# CS4244.net
KiCad netlist of a schematic drawn in EAGLE
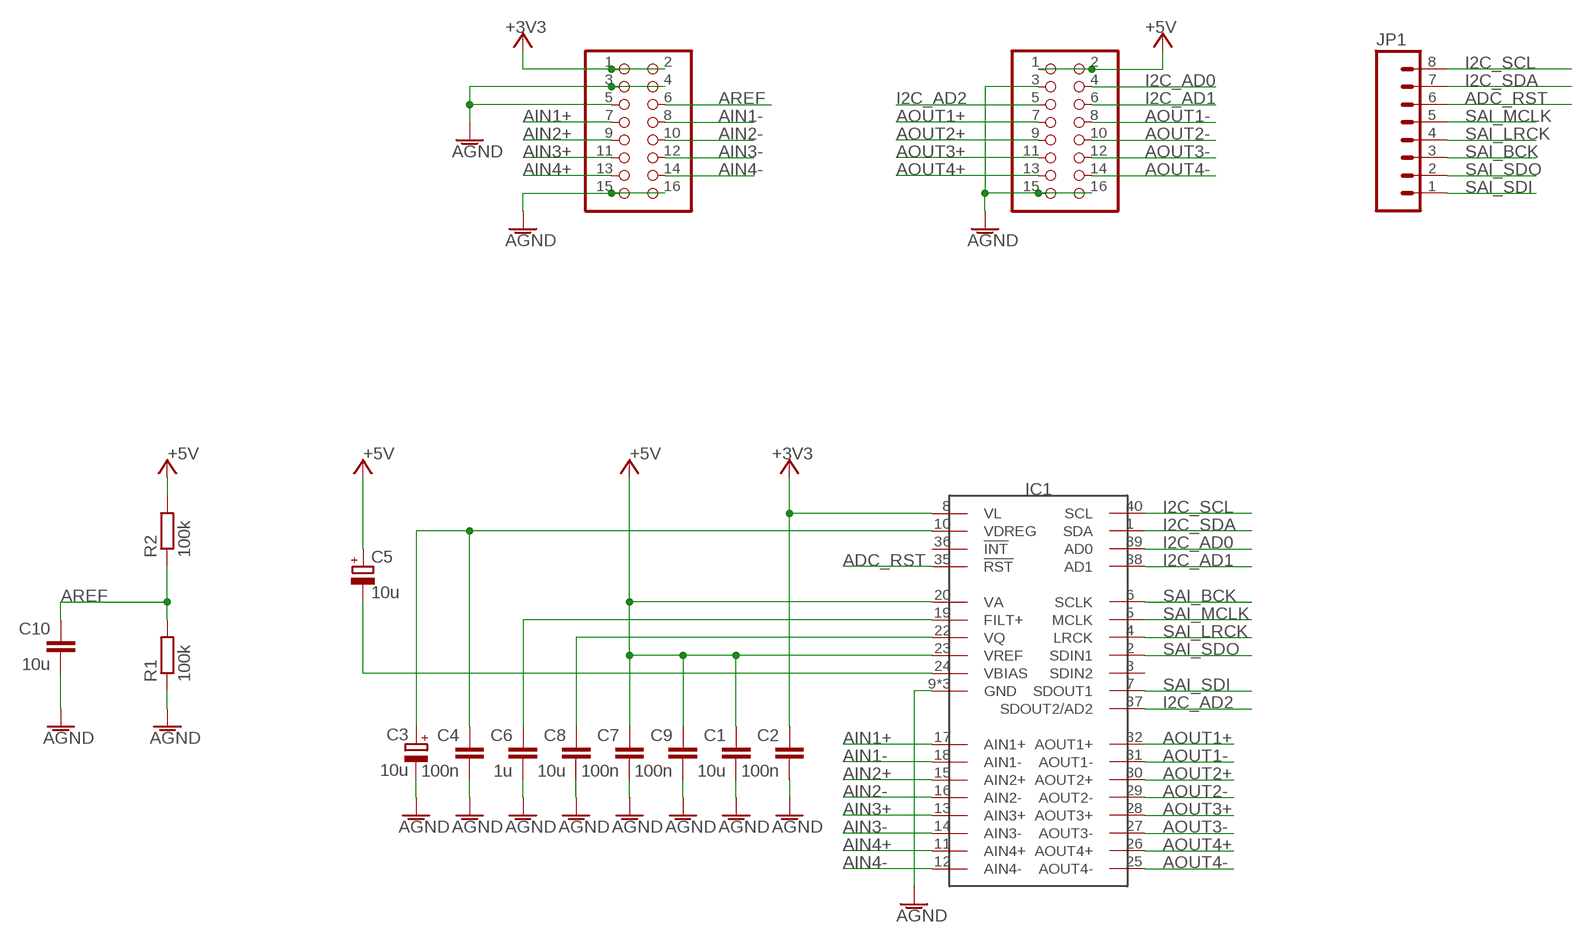
[diagram p0: schematic, sheet 1]

(export (version "E")
  (design (tool "Eeschema 10.0.6"))
  (components
    (comp (ref "C1")
      (value "10u")
      (footprint "eagle-import:C0603")
      (libsource (lib "eagle-import") (part "C-EUC0603"))
    )
    (comp (ref "C2")
      (value "100n")
      (footprint "eagle-import:C0603")
      (libsource (lib "eagle-import") (part "C-EUC0603"))
    )
    (comp (ref "C3")
      (value "10u")
      (footprint "eagle-import:UD-4X5,8_NICHICON")
      (libsource (lib "eagle-import") (part "CPOL-EUUD-4X5,8"))
    )
    (comp (ref "C4")
      (value "100n")
      (footprint "eagle-import:C0603")
      (libsource (lib "eagle-import") (part "C-EUC0603"))
    )
    (comp (ref "C5")
      (value "10u")
      (footprint "eagle-import:UD-4X5,8_NICHICON")
      (libsource (lib "eagle-import") (part "CPOL-EUUD-4X5,8"))
    )
    (comp (ref "C6")
      (value "1u")
      (footprint "eagle-import:C0603")
      (libsource (lib "eagle-import") (part "C-EUC0603"))
    )
    (comp (ref "C7")
      (value "100n")
      (footprint "eagle-import:C0603")
      (libsource (lib "eagle-import") (part "C-EUC0603"))
    )
    (comp (ref "C8")
      (value "10u")
      (footprint "eagle-import:C0603")
      (libsource (lib "eagle-import") (part "C-EUC0603"))
    )
    (comp (ref "C9")
      (value "100n")
      (footprint "eagle-import:C0603")
      (libsource (lib "eagle-import") (part "C-EUC0603"))
    )
    (comp (ref "C10")
      (value "10u")
      (footprint "eagle-import:C0603")
      (libsource (lib "eagle-import") (part "C-EUC0603"))
    )
    (comp (ref "IC1")
      (value "CS4244")
      (footprint "eagle-import:QFN50P600X600X100-41N")
      (libsource (lib "eagle-import") (part "CS4244"))
    )
    (comp (ref "JP1")
      (value "M081X08")
      (footprint "eagle-import:1X08")
      (libsource (lib "eagle-import") (part "M081X08"))
    )
    (comp (ref "JP2")
      (value "PINHD-2X8")
      (footprint "eagle-import:2X08")
      (libsource (lib "eagle-import") (part "PINHD-2X8"))
    )
    (comp (ref "JP3")
      (value "PINHD-2X8")
      (footprint "eagle-import:2X08")
      (libsource (lib "eagle-import") (part "PINHD-2X8"))
    )
    (comp (ref "R1")
      (value "100k")
      (footprint "eagle-import:0603")
      (libsource (lib "eagle-import") (part "R-EU_R0603"))
    )
    (comp (ref "R2")
      (value "100k")
      (footprint "eagle-import:0603")
      (libsource (lib "eagle-import") (part "R-EU_R0603"))
    )
  )
  (nets
    (net (code "1") (name "+3V3") (class "Default")
      (node (ref "C2") (pin "1") (pinfunction "1_1") (pintype "passive"))
      (node (ref "IC1") (pin "8") (pinfunction "VL_8") (pintype "bidirectional"))
      (node (ref "JP2") (pin "1") (pinfunction "1_1") (pintype "passive"))
      (node (ref "JP2") (pin "2") (pinfunction "2_2") (pintype "passive"))
    )
    (net (code "2") (name "+5V") (class "Default")
      (node (ref "C1") (pin "1") (pinfunction "1_1") (pintype "passive"))
      (node (ref "C5") (pin "+") (pinfunction "+_+") (pintype "passive"))
      (node (ref "C7") (pin "1") (pinfunction "1_1") (pintype "passive"))
      (node (ref "C9") (pin "1") (pinfunction "1_1") (pintype "passive"))
      (node (ref "IC1") (pin "20") (pinfunction "VA_20") (pintype "bidirectional"))
      (node (ref "IC1") (pin "23") (pinfunction "VREF_23") (pintype "bidirectional"))
      (node (ref "JP3") (pin "1") (pinfunction "1_1") (pintype "passive"))
      (node (ref "JP3") (pin "2") (pinfunction "2_2") (pintype "passive"))
      (node (ref "R2") (pin "2") (pinfunction "2_2") (pintype "passive"))
    )
    (net (code "3") (name "/ADC_RST") (class "Default")
      (node (ref "IC1") (pin "35") (pinfunction "~{RST}_35") (pintype "bidirectional"))
      (node (ref "JP1") (pin "6") (pinfunction "6_6") (pintype "passive"))
    )
    (net (code "4") (name "/AIN1+") (class "Default")
      (node (ref "IC1") (pin "17") (pinfunction "AIN1+_17") (pintype "bidirectional"))
      (node (ref "JP2") (pin "7") (pinfunction "7_7") (pintype "passive"))
    )
    (net (code "5") (name "/AIN1-") (class "Default")
      (node (ref "IC1") (pin "18") (pinfunction "AIN1-_18") (pintype "bidirectional"))
      (node (ref "JP2") (pin "8") (pinfunction "8_8") (pintype "passive"))
    )
    (net (code "6") (name "/AIN2+") (class "Default")
      (node (ref "IC1") (pin "15") (pinfunction "AIN2+_15") (pintype "bidirectional"))
      (node (ref "JP2") (pin "9") (pinfunction "9_9") (pintype "passive"))
    )
    (net (code "7") (name "/AIN2-") (class "Default")
      (node (ref "IC1") (pin "16") (pinfunction "AIN2-_16") (pintype "bidirectional"))
      (node (ref "JP2") (pin "10") (pinfunction "10_10") (pintype "passive"))
    )
    (net (code "8") (name "/AIN3+") (class "Default")
      (node (ref "IC1") (pin "13") (pinfunction "AIN3+_13") (pintype "bidirectional"))
      (node (ref "JP2") (pin "11") (pinfunction "11_11") (pintype "passive"))
    )
    (net (code "9") (name "/AIN3-") (class "Default")
      (node (ref "IC1") (pin "14") (pinfunction "AIN3-_14") (pintype "bidirectional"))
      (node (ref "JP2") (pin "12") (pinfunction "12_12") (pintype "passive"))
    )
    (net (code "10") (name "/AIN4+") (class "Default")
      (node (ref "IC1") (pin "11") (pinfunction "AIN4+_11") (pintype "bidirectional"))
      (node (ref "JP2") (pin "13") (pinfunction "13_13") (pintype "passive"))
    )
    (net (code "11") (name "/AIN4-") (class "Default")
      (node (ref "IC1") (pin "12") (pinfunction "AIN4-_12") (pintype "bidirectional"))
      (node (ref "JP2") (pin "14") (pinfunction "14_14") (pintype "passive"))
    )
    (net (code "12") (name "/AOUT1+") (class "Default")
      (node (ref "IC1") (pin "32") (pinfunction "AOUT1+_32") (pintype "bidirectional"))
      (node (ref "JP3") (pin "7") (pinfunction "7_7") (pintype "passive"))
    )
    (net (code "13") (name "/AOUT1-") (class "Default")
      (node (ref "IC1") (pin "31") (pinfunction "AOUT1-_31") (pintype "bidirectional"))
      (node (ref "JP3") (pin "8") (pinfunction "8_8") (pintype "passive"))
    )
    (net (code "14") (name "/AOUT2+") (class "Default")
      (node (ref "IC1") (pin "30") (pinfunction "AOUT2+_30") (pintype "bidirectional"))
      (node (ref "JP3") (pin "9") (pinfunction "9_9") (pintype "passive"))
    )
    (net (code "15") (name "/AOUT2-") (class "Default")
      (node (ref "IC1") (pin "29") (pinfunction "AOUT2-_29") (pintype "bidirectional"))
      (node (ref "JP3") (pin "10") (pinfunction "10_10") (pintype "passive"))
    )
    (net (code "16") (name "/AOUT3+") (class "Default")
      (node (ref "IC1") (pin "28") (pinfunction "AOUT3+_28") (pintype "bidirectional"))
      (node (ref "JP3") (pin "11") (pinfunction "11_11") (pintype "passive"))
    )
    (net (code "17") (name "/AOUT3-") (class "Default")
      (node (ref "IC1") (pin "27") (pinfunction "AOUT3-_27") (pintype "bidirectional"))
      (node (ref "JP3") (pin "12") (pinfunction "12_12") (pintype "passive"))
    )
    (net (code "18") (name "/AOUT4+") (class "Default")
      (node (ref "IC1") (pin "26") (pinfunction "AOUT4+_26") (pintype "bidirectional"))
      (node (ref "JP3") (pin "13") (pinfunction "13_13") (pintype "passive"))
    )
    (net (code "19") (name "/AOUT4-") (class "Default")
      (node (ref "IC1") (pin "25") (pinfunction "AOUT4-_25") (pintype "bidirectional"))
      (node (ref "JP3") (pin "14") (pinfunction "14_14") (pintype "passive"))
    )
    (net (code "20") (name "/AREF") (class "Default")
      (node (ref "C10") (pin "1") (pinfunction "1_1") (pintype "passive"))
      (node (ref "JP2") (pin "6") (pinfunction "6_6") (pintype "passive"))
      (node (ref "R1") (pin "2") (pinfunction "2_2") (pintype "passive"))
      (node (ref "R2") (pin "1") (pinfunction "1_1") (pintype "passive"))
    )
    (net (code "21") (name "/I2C_AD0") (class "Default")
      (node (ref "IC1") (pin "39") (pinfunction "AD0_39") (pintype "bidirectional"))
      (node (ref "JP3") (pin "4") (pinfunction "4_4") (pintype "passive"))
    )
    (net (code "22") (name "/I2C_AD1") (class "Default")
      (node (ref "IC1") (pin "38") (pinfunction "AD1_38") (pintype "bidirectional"))
      (node (ref "JP3") (pin "6") (pinfunction "6_6") (pintype "passive"))
    )
    (net (code "23") (name "/I2C_AD2") (class "Default")
      (node (ref "IC1") (pin "37") (pinfunction "SDOUT2/AD2_37") (pintype "bidirectional"))
      (node (ref "JP3") (pin "5") (pinfunction "5_5") (pintype "passive"))
    )
    (net (code "24") (name "/I2C_SCL") (class "Default")
      (node (ref "IC1") (pin "40") (pinfunction "SCL_40") (pintype "bidirectional"))
      (node (ref "JP1") (pin "8") (pinfunction "8_8") (pintype "passive"))
    )
    (net (code "25") (name "/I2C_SDA") (class "Default")
      (node (ref "IC1") (pin "1") (pinfunction "SDA_1") (pintype "bidirectional"))
      (node (ref "JP1") (pin "7") (pinfunction "7_7") (pintype "passive"))
    )
    (net (code "26") (name "/SAI_BCK") (class "Default")
      (node (ref "IC1") (pin "6") (pinfunction "SCLK_6") (pintype "bidirectional"))
      (node (ref "JP1") (pin "3") (pinfunction "3_3") (pintype "passive"))
    )
    (net (code "27") (name "/SAI_LRCK") (class "Default")
      (node (ref "IC1") (pin "4") (pinfunction "LRCK_4") (pintype "bidirectional"))
      (node (ref "JP1") (pin "4") (pinfunction "4_4") (pintype "passive"))
    )
    (net (code "28") (name "/SAI_MCLK") (class "Default")
      (node (ref "IC1") (pin "5") (pinfunction "MCLK_5") (pintype "bidirectional"))
      (node (ref "JP1") (pin "5") (pinfunction "5_5") (pintype "passive"))
    )
    (net (code "29") (name "/SAI_SDI") (class "Default")
      (node (ref "IC1") (pin "7") (pinfunction "SDOUT1_7") (pintype "bidirectional"))
      (node (ref "JP1") (pin "1") (pinfunction "1_1") (pintype "passive"))
    )
    (net (code "30") (name "/SAI_SDO") (class "Default")
      (node (ref "IC1") (pin "2") (pinfunction "SDIN1_2") (pintype "bidirectional"))
      (node (ref "JP1") (pin "2") (pinfunction "2_2") (pintype "passive"))
    )
    (net (code "31") (name "AGND") (class "Default")
      (node (ref "C1") (pin "2") (pinfunction "2_2") (pintype "passive"))
      (node (ref "C10") (pin "2") (pinfunction "2_2") (pintype "passive"))
      (node (ref "C2") (pin "2") (pinfunction "2_2") (pintype "passive"))
      (node (ref "C3") (pin "-") (pinfunction "-_-") (pintype "passive"))
      (node (ref "C4") (pin "2") (pinfunction "2_2") (pintype "passive"))
      (node (ref "C6") (pin "2") (pinfunction "2_2") (pintype "passive"))
      (node (ref "C7") (pin "2") (pinfunction "2_2") (pintype "passive"))
      (node (ref "C8") (pin "2") (pinfunction "2_2") (pintype "passive"))
      (node (ref "C9") (pin "2") (pinfunction "2_2") (pintype "passive"))
      (node (ref "IC1") (pin "21") (pinfunction "GND_21") (pintype "bidirectional"))
      (node (ref "IC1") (pin "41") (pinfunction "GND_41") (pintype "bidirectional"))
      (node (ref "IC1") (pin "9") (pinfunction "GND_9") (pintype "bidirectional"))
      (node (ref "JP2") (pin "15") (pinfunction "15_15") (pintype "passive"))
      (node (ref "JP2") (pin "16") (pinfunction "16_16") (pintype "passive"))
      (node (ref "JP2") (pin "3") (pinfunction "3_3") (pintype "passive"))
      (node (ref "JP2") (pin "4") (pinfunction "4_4") (pintype "passive"))
      (node (ref "JP2") (pin "5") (pinfunction "5_5") (pintype "passive"))
      (node (ref "JP3") (pin "15") (pinfunction "15_15") (pintype "passive"))
      (node (ref "JP3") (pin "16") (pinfunction "16_16") (pintype "passive"))
      (node (ref "JP3") (pin "3") (pinfunction "3_3") (pintype "passive"))
      (node (ref "R1") (pin "1") (pinfunction "1_1") (pintype "passive"))
    )
    (net (code "32") (name "Net-(IC1-FILT+)") (class "Default")
      (node (ref "C6") (pin "1") (pinfunction "1_1") (pintype "passive"))
      (node (ref "IC1") (pin "19") (pinfunction "FILT+_19") (pintype "bidirectional"))
    )
    (net (code "33") (name "Net-(IC1-VBIAS)") (class "Default")
      (node (ref "C5") (pin "-") (pinfunction "-_-") (pintype "passive"))
      (node (ref "IC1") (pin "24") (pinfunction "VBIAS_24") (pintype "bidirectional"))
    )
    (net (code "34") (name "Net-(IC1-VDREG)") (class "Default")
      (node (ref "C3") (pin "+") (pinfunction "+_+") (pintype "passive"))
      (node (ref "C4") (pin "1") (pinfunction "1_1") (pintype "passive"))
      (node (ref "IC1") (pin "10") (pinfunction "VDREG_10") (pintype "bidirectional"))
    )
    (net (code "35") (name "Net-(IC1-VQ)") (class "Default")
      (node (ref "C8") (pin "1") (pinfunction "1_1") (pintype "passive"))
      (node (ref "IC1") (pin "22") (pinfunction "VQ_22") (pintype "bidirectional"))
    )
    (net (code "36") (name "unconnected-(IC1-SDIN2-Pad3)") (class "Default")
      (node (ref "IC1") (pin "3") (pinfunction "SDIN2_3") (pintype "bidirectional"))
    )
    (net (code "37") (name "unconnected-(IC1-~{INT}-Pad36)") (class "Default")
      (node (ref "IC1") (pin "36") (pinfunction "~{INT}_36") (pintype "bidirectional"))
    )
  )
)
